# 6relayBoard.net
KiCad netlist of a schematic drawn in EAGLE
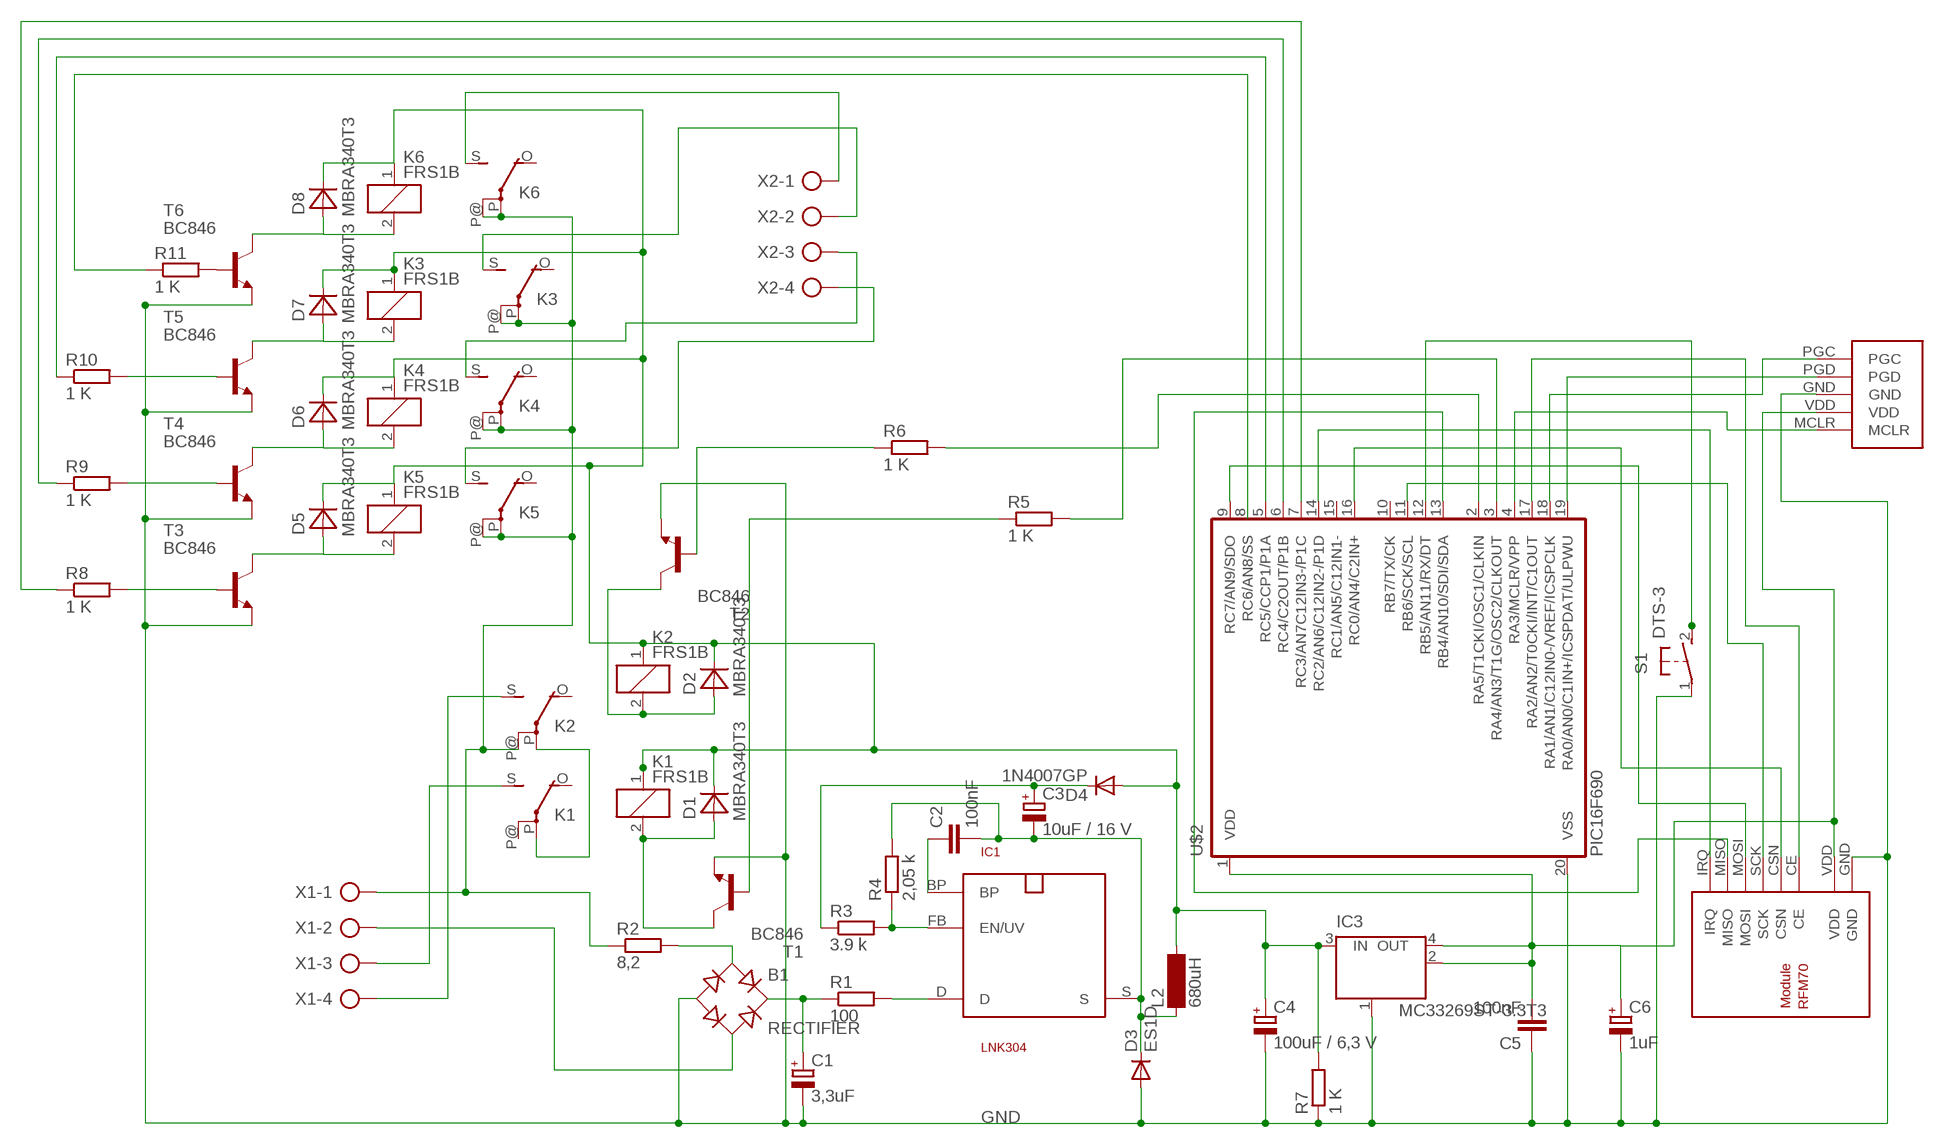
[diagram p0: schematic, sheet 1]

(export (version "E")
  (design (tool "Eeschema 10.0.6"))
  (components
    (comp (ref "B1")
      (value "RECTIFIER")
      (footprint "eagle-import:TO-269AA")
      (libsource (lib "eagle-import") (part "RECTIFIER-S40"))
    )
    (comp (ref "C1")
      (value "3,3uF")
      (footprint "eagle-import:E5-10,5")
      (libsource (lib "eagle-import") (part "CPOL-EUE5-10.5"))
    )
    (comp (ref "C2")
      (value "100nF")
      (footprint "eagle-import:C2012")
      (libsource (lib "eagle-import") (part "C-EUC2012"))
    )
    (comp (ref "C3")
      (value "10uF / 16 V")
      (footprint "eagle-import:SMC_C")
      (libsource (lib "eagle-import") (part "CPOL-EUSMCC"))
    )
    (comp (ref "C4")
      (value "100uF / 6,3 V")
      (footprint "eagle-import:E2,5-5")
      (libsource (lib "eagle-import") (part "CPOL-EUE2.5-5"))
    )
    (comp (ref "C5")
      (value "100nF")
      (footprint "eagle-import:C2012")
      (libsource (lib "eagle-import") (part "C-EUC2012"))
    )
    (comp (ref "C6")
      (value "1uF")
      (footprint "eagle-import:SMC_A")
      (libsource (lib "eagle-import") (part "CPOL-EUSMCA"))
    )
    (comp (ref "D1")
      (value "MBRA340T3")
      (footprint "eagle-import:SMA")
      (libsource (lib "eagle-import") (part "MBRA340T3"))
    )
    (comp (ref "D2")
      (value "MBRA340T3")
      (footprint "eagle-import:SMA")
      (libsource (lib "eagle-import") (part "MBRA340T3"))
    )
    (comp (ref "D3")
      (value "ES1D")
      (footprint "eagle-import:DO214AC")
      (libsource (lib "eagle-import") (part "DIODE-DO214AC"))
    )
    (comp (ref "D4")
      (value "1N4007GP")
      (footprint "eagle-import:DO214AA")
      (libsource (lib "eagle-import") (part "DIODE-DO214AA"))
    )
    (comp (ref "D5")
      (value "MBRA340T3")
      (footprint "eagle-import:SMA")
      (libsource (lib "eagle-import") (part "MBRA340T3"))
    )
    (comp (ref "D6")
      (value "MBRA340T3")
      (footprint "eagle-import:SMA")
      (libsource (lib "eagle-import") (part "MBRA340T3"))
    )
    (comp (ref "D7")
      (value "MBRA340T3")
      (footprint "eagle-import:SMA")
      (libsource (lib "eagle-import") (part "MBRA340T3"))
    )
    (comp (ref "D8")
      (value "MBRA340T3")
      (footprint "eagle-import:SMA")
      (libsource (lib "eagle-import") (part "MBRA340T3"))
    )
    (comp (ref "IC1")
      (value "LNK304")
      (footprint "eagle-import:SO-8C")
      (libsource (lib "eagle-import") (part "SO-8C"))
    )
    (comp (ref "IC3")
      (value "MC33269ST-3.3T3")
      (footprint "eagle-import:SOT223")
      (libsource (lib "eagle-import") (part "MC33269ST-3.3T3"))
    )
    (comp (ref "K1")
      (value "FRS1B")
      (footprint "eagle-import:FRS1B")
      (libsource (lib "eagle-import") (part "FRS1B"))
    )
    (comp (ref "K2")
      (value "FRS1B")
      (footprint "eagle-import:FRS1B")
      (fields (field (name "OC_FARNELL") "unknown") (field (name "OC_NEWARK") "unknown"))
      (libsource (lib "eagle-import") (part "FRS1B"))
    )
    (comp (ref "K3")
      (value "FRS1B")
      (footprint "eagle-import:FRS1B")
      (fields (field (name "OC_FARNELL") "unknown") (field (name "OC_NEWARK") "unknown"))
      (libsource (lib "eagle-import") (part "FRS1B"))
    )
    (comp (ref "K4")
      (value "FRS1B")
      (footprint "eagle-import:FRS1B")
      (fields (field (name "OC_FARNELL") "unknown") (field (name "OC_NEWARK") "unknown"))
      (libsource (lib "eagle-import") (part "FRS1B"))
    )
    (comp (ref "K5")
      (value "FRS1B")
      (footprint "eagle-import:FRS1B")
      (fields (field (name "OC_FARNELL") "unknown") (field (name "OC_NEWARK") "unknown"))
      (libsource (lib "eagle-import") (part "FRS1B"))
    )
    (comp (ref "K6")
      (value "FRS1B")
      (footprint "eagle-import:FRS1B")
      (fields (field (name "OC_FARNELL") "unknown") (field (name "OC_NEWARK") "unknown"))
      (libsource (lib "eagle-import") (part "FRS1B"))
    )
    (comp (ref "L2")
      (value "680uH")
      (footprint "eagle-import:BS11")
      (libsource (lib "eagle-import") (part "BS11"))
    )
    (comp (ref "R1")
      (value "100")
      (footprint "eagle-import:R2512W")
      (libsource (lib "eagle-import") (part "R-EU_R2512W"))
    )
    (comp (ref "R2")
      (value "8,2")
      (footprint "eagle-import:0411_12")
      (libsource (lib "eagle-import") (part "R-EU_0411/12"))
    )
    (comp (ref "R3")
      (value "3.9 k")
      (footprint "eagle-import:M2012")
      (libsource (lib "eagle-import") (part "R-EU_M2012"))
    )
    (comp (ref "R4")
      (value "2,05 k")
      (footprint "eagle-import:M2012")
      (libsource (lib "eagle-import") (part "R-EU_M2012"))
    )
    (comp (ref "R5")
      (value "1 K")
      (footprint "eagle-import:M2012")
      (libsource (lib "eagle-import") (part "R-EU_M2012"))
    )
    (comp (ref "R6")
      (value "1 K")
      (footprint "eagle-import:M2012")
      (libsource (lib "eagle-import") (part "R-EU_M2012"))
    )
    (comp (ref "R7")
      (value "1 K")
      (footprint "eagle-import:M2012")
      (libsource (lib "eagle-import") (part "R-EU_M2012"))
    )
    (comp (ref "R8")
      (value "1 K")
      (footprint "eagle-import:M2012")
      (libsource (lib "eagle-import") (part "R-EU_M2012"))
    )
    (comp (ref "R9")
      (value "1 K")
      (footprint "eagle-import:M2012")
      (libsource (lib "eagle-import") (part "R-EU_M2012"))
    )
    (comp (ref "R10")
      (value "1 K")
      (footprint "eagle-import:M2012")
      (libsource (lib "eagle-import") (part "R-EU_M2012"))
    )
    (comp (ref "R11")
      (value "1 K")
      (footprint "eagle-import:M2012")
      (libsource (lib "eagle-import") (part "R-EU_M2012"))
    )
    (comp (ref "S1")
      (value "DTS-3")
      (footprint "eagle-import:DTS-3")
      (libsource (lib "eagle-import") (part "DTS-3"))
    )
    (comp (ref "T1")
      (value "BC846")
      (footprint "eagle-import:SOT23")
      (libsource (lib "eagle-import") (part "BC846"))
    )
    (comp (ref "T2")
      (value "BC846")
      (footprint "eagle-import:SOT23")
      (libsource (lib "eagle-import") (part "BC846"))
    )
    (comp (ref "T3")
      (value "BC846")
      (footprint "eagle-import:SOT23")
      (libsource (lib "eagle-import") (part "BC846"))
    )
    (comp (ref "T4")
      (value "BC846")
      (footprint "eagle-import:SOT23")
      (libsource (lib "eagle-import") (part "BC846"))
    )
    (comp (ref "T5")
      (value "BC846")
      (footprint "eagle-import:SOT23")
      (libsource (lib "eagle-import") (part "BC846"))
    )
    (comp (ref "T6")
      (value "BC846")
      (footprint "eagle-import:SOT23")
      (libsource (lib "eagle-import") (part "BC846"))
    )
    (comp (ref "U$1")
      (value "RFM70")
      (footprint "eagle-import:RFM70")
      (libsource (lib "eagle-import") (part "RFM70"))
    )
    (comp (ref "U$2")
      (value "PIC16F690")
      (footprint "eagle-import:SSOP20")
      (libsource (lib "eagle-import") (part "PIC16F690"))
    )
    (comp (ref "U$3")
      (value "PROGRAMMINGHEADERDIP")
      (footprint "eagle-import:PROGHEADER")
      (libsource (lib "eagle-import") (part "PROGRAMMINGHEADERDIP"))
    )
    (comp (ref "X1")
      (value "AK500/4")
      (footprint "eagle-import:AK500_4")
      (libsource (lib "eagle-import") (part "AK500/4"))
    )
    (comp (ref "X2")
      (value "AK500/4")
      (footprint "eagle-import:AK500_4")
      (fields (field (name "OC_FARNELL") "unknown") (field (name "OC_NEWARK") "unknown"))
      (libsource (lib "eagle-import") (part "AK500/4"))
    )
  )
  (nets
    (net (code "1") (name "/GND") (class "Default")
      (node (ref "B1") (pin "-") (pinfunction "-_-") (pintype "passive"))
      (node (ref "C1") (pin "-") (pinfunction "-_-") (pintype "passive"))
      (node (ref "C4") (pin "-") (pinfunction "-_-") (pintype "passive"))
      (node (ref "C5") (pin "1") (pinfunction "1_1") (pintype "passive"))
      (node (ref "C6") (pin "-") (pinfunction "-_-") (pintype "passive"))
      (node (ref "D3") (pin "A") (pinfunction "A_A") (pintype "passive"))
      (node (ref "IC3") (pin "1") (pinfunction "GND/ADJ_1") (pintype "input"))
      (node (ref "R7") (pin "1") (pinfunction "1_1") (pintype "passive"))
      (node (ref "S1") (pin "1") (pinfunction "1_1") (pintype "passive"))
      (node (ref "T1") (pin "2") (pinfunction "E_2") (pintype "passive"))
      (node (ref "T2") (pin "2") (pinfunction "E_2") (pintype "passive"))
      (node (ref "T3") (pin "2") (pinfunction "E_2") (pintype "passive"))
      (node (ref "T4") (pin "2") (pinfunction "E_2") (pintype "passive"))
      (node (ref "T5") (pin "2") (pinfunction "E_2") (pintype "passive"))
      (node (ref "T6") (pin "2") (pinfunction "E_2") (pintype "passive"))
      (node (ref "U$1") (pin "GND") (pinfunction "GND_GND") (pintype "power_in"))
      (node (ref "U$2") (pin "20") (pinfunction "VSS_20") (pintype "power_in"))
      (node (ref "U$3") (pin "GND") (pinfunction "GND_GND") (pintype "power_in"))
    )
    (net (code "2") (name "Net-(B1-Pad+)") (class "Default")
      (node (ref "B1") (pin "+") (pinfunction "+_+") (pintype "passive"))
      (node (ref "C1") (pin "+") (pinfunction "+_+") (pintype "passive"))
      (node (ref "R1") (pin "1") (pinfunction "1_1") (pintype "passive"))
    )
    (net (code "3") (name "Net-(B1-PadAC1)") (class "Default")
      (node (ref "B1") (pin "AC1") (pinfunction "AC1_AC1") (pintype "passive"))
      (node (ref "R2") (pin "2") (pinfunction "2_2") (pintype "passive"))
    )
    (net (code "4") (name "Net-(C2-Pad1)") (class "Default")
      (node (ref "C2") (pin "1") (pinfunction "1_1") (pintype "passive"))
      (node (ref "IC1") (pin "BP") (pinfunction "BP_BP") (pintype "passive"))
    )
    (net (code "5") (name "Net-(C2-Pad2)") (class "Default")
      (node (ref "C2") (pin "2") (pinfunction "2_2") (pintype "passive"))
      (node (ref "C3") (pin "-") (pinfunction "-_-") (pintype "passive"))
      (node (ref "D3") (pin "C") (pinfunction "C_C") (pintype "passive"))
      (node (ref "IC1") (pin "S") (pinfunction "S_S") (pintype "power_in"))
      (node (ref "L2") (pin "1") (pinfunction "1_1") (pintype "passive"))
      (node (ref "R4") (pin "2") (pinfunction "2_2") (pintype "passive"))
    )
    (net (code "6") (name "Net-(C3-Pad+)") (class "Default")
      (node (ref "C3") (pin "+") (pinfunction "+_+") (pintype "passive"))
      (node (ref "D4") (pin "C") (pinfunction "C_C") (pintype "passive"))
      (node (ref "R3") (pin "1") (pinfunction "1_1") (pintype "passive"))
    )
    (net (code "7") (name "Net-(IC1-EN{slash}UV)") (class "Default")
      (node (ref "IC1") (pin "FB") (pinfunction "EN/UV_FB") (pintype "input"))
      (node (ref "R3") (pin "2") (pinfunction "2_2") (pintype "passive"))
      (node (ref "R4") (pin "1") (pinfunction "1_1") (pintype "passive"))
    )
    (net (code "8") (name "Net-(IC1-PadD)") (class "Default")
      (node (ref "IC1") (pin "D") (pinfunction "D_D") (pintype "open_collector"))
      (node (ref "R1") (pin "2") (pinfunction "2_2") (pintype "passive"))
    )
    (net (code "9") (name "Net-(IC3-IN)") (class "Default")
      (node (ref "C4") (pin "+") (pinfunction "+_+") (pintype "passive"))
      (node (ref "D1") (pin "C") (pinfunction "C_C") (pintype "passive"))
      (node (ref "D2") (pin "C") (pinfunction "C_C") (pintype "passive"))
      (node (ref "D4") (pin "A") (pinfunction "A_A") (pintype "passive"))
      (node (ref "D5") (pin "C") (pinfunction "C_C") (pintype "passive"))
      (node (ref "D6") (pin "C") (pinfunction "C_C") (pintype "passive"))
      (node (ref "D7") (pin "C") (pinfunction "C_C") (pintype "passive"))
      (node (ref "D8") (pin "C") (pinfunction "C_C") (pintype "passive"))
      (node (ref "IC3") (pin "3") (pinfunction "IN_3") (pintype "input"))
      (node (ref "K1") (pin "1") (pinfunction "1_1") (pintype "passive"))
      (node (ref "K2") (pin "1") (pinfunction "1_1") (pintype "passive"))
      (node (ref "K3") (pin "1") (pinfunction "1_1") (pintype "passive"))
      (node (ref "K4") (pin "1") (pinfunction "1_1") (pintype "passive"))
      (node (ref "K5") (pin "1") (pinfunction "1_1") (pintype "passive"))
      (node (ref "K6") (pin "1") (pinfunction "1_1") (pintype "passive"))
      (node (ref "L2") (pin "2") (pinfunction "2_2") (pintype "passive"))
      (node (ref "R7") (pin "2") (pinfunction "2_2") (pintype "passive"))
    )
    (net (code "10") (name "Net-(K1-PadP)") (class "Default")
      (node (ref "K1") (pin "P") (pinfunction "P_P") (pintype "passive"))
      (node (ref "K2") (pin "P") (pinfunction "P_P") (pintype "passive"))
    )
    (net (code "11") (name "Net-(T1-B)") (class "Default")
      (node (ref "R5") (pin "1") (pinfunction "1_1") (pintype "passive"))
      (node (ref "T1") (pin "1") (pinfunction "B_1") (pintype "passive"))
    )
    (net (code "12") (name "Net-(T1-C)") (class "Default")
      (node (ref "D1") (pin "A") (pinfunction "A_A") (pintype "passive"))
      (node (ref "K1") (pin "2") (pinfunction "2_2") (pintype "passive"))
      (node (ref "T1") (pin "3") (pinfunction "C_3") (pintype "passive"))
    )
    (net (code "13") (name "Net-(T2-B)") (class "Default")
      (node (ref "R6") (pin "1") (pinfunction "1_1") (pintype "passive"))
      (node (ref "T2") (pin "1") (pinfunction "B_1") (pintype "passive"))
    )
    (net (code "14") (name "Net-(T2-C)") (class "Default")
      (node (ref "D2") (pin "A") (pinfunction "A_A") (pintype "passive"))
      (node (ref "K2") (pin "2") (pinfunction "2_2") (pintype "passive"))
      (node (ref "T2") (pin "3") (pinfunction "C_3") (pintype "passive"))
    )
    (net (code "15") (name "Net-(T3-B)") (class "Default")
      (node (ref "R8") (pin "2") (pinfunction "2_2") (pintype "passive"))
      (node (ref "T3") (pin "1") (pinfunction "B_1") (pintype "passive"))
    )
    (net (code "16") (name "Net-(T3-C)") (class "Default")
      (node (ref "D5") (pin "A") (pinfunction "A_A") (pintype "passive"))
      (node (ref "K5") (pin "2") (pinfunction "2_2") (pintype "passive"))
      (node (ref "T3") (pin "3") (pinfunction "C_3") (pintype "passive"))
    )
    (net (code "17") (name "Net-(T4-B)") (class "Default")
      (node (ref "R9") (pin "2") (pinfunction "2_2") (pintype "passive"))
      (node (ref "T4") (pin "1") (pinfunction "B_1") (pintype "passive"))
    )
    (net (code "18") (name "Net-(T4-C)") (class "Default")
      (node (ref "D6") (pin "A") (pinfunction "A_A") (pintype "passive"))
      (node (ref "K4") (pin "2") (pinfunction "2_2") (pintype "passive"))
      (node (ref "T4") (pin "3") (pinfunction "C_3") (pintype "passive"))
    )
    (net (code "19") (name "Net-(T5-B)") (class "Default")
      (node (ref "R10") (pin "2") (pinfunction "2_2") (pintype "passive"))
      (node (ref "T5") (pin "1") (pinfunction "B_1") (pintype "passive"))
    )
    (net (code "20") (name "Net-(T5-C)") (class "Default")
      (node (ref "D7") (pin "A") (pinfunction "A_A") (pintype "passive"))
      (node (ref "K3") (pin "2") (pinfunction "2_2") (pintype "passive"))
      (node (ref "T5") (pin "3") (pinfunction "C_3") (pintype "passive"))
    )
    (net (code "21") (name "Net-(T6-B)") (class "Default")
      (node (ref "R11") (pin "2") (pinfunction "2_2") (pintype "passive"))
      (node (ref "T6") (pin "1") (pinfunction "B_1") (pintype "passive"))
    )
    (net (code "22") (name "Net-(T6-C)") (class "Default")
      (node (ref "D8") (pin "A") (pinfunction "A_A") (pintype "passive"))
      (node (ref "K6") (pin "2") (pinfunction "2_2") (pintype "passive"))
      (node (ref "T6") (pin "3") (pinfunction "C_3") (pintype "passive"))
    )
    (net (code "23") (name "Net-(U$2-RA0{slash}AN0{slash}C1IN+{slash}ICSPDAT{slash}ULPWU)") (class "Default")
      (node (ref "U$2") (pin "19") (pinfunction "RA0/AN0/C1IN+/ICSPDAT/ULPWU_19") (pintype "bidirectional"))
      (node (ref "U$3") (pin "PGD") (pinfunction "PGD_PGD") (pintype "bidirectional"))
    )
    (net (code "24") (name "Net-(U$2-RA1{slash}AN1{slash}C12IN0-{slash}VREF{slash}ICSPCLK)") (class "Default")
      (node (ref "U$2") (pin "18") (pinfunction "RA1/AN1/C12IN0-/VREF/ICSPCLK_18") (pintype "bidirectional"))
      (node (ref "U$3") (pin "PGC") (pinfunction "PGC_PGC") (pintype "bidirectional"))
    )
    (net (code "25") (name "Net-(U$2-RA2{slash}AN2{slash}T0CKI{slash}INT{slash}C1OUT)") (class "Default")
      (node (ref "U$1") (pin "CE") (pinfunction "CE_CE") (pintype "bidirectional"))
      (node (ref "U$2") (pin "17") (pinfunction "RA2/AN2/T0CKI/INT/C1OUT_17") (pintype "bidirectional"))
    )
    (net (code "26") (name "Net-(U$2-RA3{slash}MCLR{slash}VPP)") (class "Default")
      (node (ref "U$2") (pin "4") (pinfunction "RA3/MCLR/VPP_4") (pintype "bidirectional"))
      (node (ref "U$3") (pin "MCLR") (pinfunction "MCLR_MCLR") (pintype "output"))
    )
    (net (code "27") (name "Net-(U$2-RA4{slash}AN3{slash}T1G{slash}OSC2{slash}CLKOUT)") (class "Default")
      (node (ref "R5") (pin "2") (pinfunction "2_2") (pintype "passive"))
      (node (ref "U$2") (pin "3") (pinfunction "RA4/AN3/T1G/OSC2/CLKOUT_3") (pintype "bidirectional"))
    )
    (net (code "28") (name "Net-(U$2-RA5{slash}T1CKI{slash}OSC1{slash}CLKIN)") (class "Default")
      (node (ref "R6") (pin "2") (pinfunction "2_2") (pintype "passive"))
      (node (ref "U$2") (pin "2") (pinfunction "RA5/T1CKI/OSC1/CLKIN_2") (pintype "bidirectional"))
    )
    (net (code "29") (name "Net-(U$2-RB4{slash}AN10{slash}SDI{slash}SDA)") (class "Default")
      (node (ref "U$1") (pin "MISO") (pinfunction "MISO_MISO") (pintype "bidirectional"))
      (node (ref "U$2") (pin "13") (pinfunction "RB4/AN10/SDI/SDA_13") (pintype "bidirectional"))
    )
    (net (code "30") (name "Net-(U$2-RB5{slash}AN11{slash}RX{slash}DT)") (class "Default")
      (node (ref "S1") (pin "2") (pinfunction "2_2") (pintype "passive"))
      (node (ref "U$2") (pin "12") (pinfunction "RB5/AN11/RX/DT_12") (pintype "bidirectional"))
    )
    (net (code "31") (name "Net-(U$2-RB6{slash}SCK{slash}SCL)") (class "Default")
      (node (ref "U$1") (pin "SCK") (pinfunction "SCK_SCK") (pintype "bidirectional"))
      (node (ref "U$2") (pin "11") (pinfunction "RB6/SCK/SCL_11") (pintype "bidirectional"))
    )
    (net (code "32") (name "Net-(U$2-RC0{slash}AN4{slash}C2IN+)") (class "Default")
      (node (ref "U$1") (pin "CSN") (pinfunction "CSN_CSN") (pintype "bidirectional"))
      (node (ref "U$2") (pin "16") (pinfunction "RC0/AN4/C2IN+_16") (pintype "bidirectional"))
    )
    (net (code "33") (name "Net-(U$2-RC2{slash}AN6{slash}C12IN2-{slash}P1D)") (class "Default")
      (node (ref "U$1") (pin "IRQ") (pinfunction "IRQ_IRQ") (pintype "bidirectional"))
      (node (ref "U$2") (pin "14") (pinfunction "RC2/AN6/C12IN2-/P1D_14") (pintype "bidirectional"))
    )
    (net (code "34") (name "Net-(U$2-RC3{slash}AN7C12IN3-{slash}P1C)") (class "Default")
      (node (ref "R8") (pin "1") (pinfunction "1_1") (pintype "passive"))
      (node (ref "U$2") (pin "7") (pinfunction "RC3/AN7C12IN3-/P1C_7") (pintype "bidirectional"))
    )
    (net (code "35") (name "Net-(U$2-RC4{slash}C2OUT{slash}P1B)") (class "Default")
      (node (ref "R9") (pin "1") (pinfunction "1_1") (pintype "passive"))
      (node (ref "U$2") (pin "6") (pinfunction "RC4/C2OUT/P1B_6") (pintype "bidirectional"))
    )
    (net (code "36") (name "Net-(U$2-RC5{slash}CCP1{slash}P1A)") (class "Default")
      (node (ref "R10") (pin "1") (pinfunction "1_1") (pintype "passive"))
      (node (ref "U$2") (pin "5") (pinfunction "RC5/CCP1/P1A_5") (pintype "bidirectional"))
    )
    (net (code "37") (name "Net-(U$2-RC6{slash}AN8{slash}SS)") (class "Default")
      (node (ref "R11") (pin "1") (pinfunction "1_1") (pintype "passive"))
      (node (ref "U$2") (pin "8") (pinfunction "RC6/AN8/SS_8") (pintype "bidirectional"))
    )
    (net (code "38") (name "Net-(U$2-RC7{slash}AN9{slash}SDO)") (class "Default")
      (node (ref "U$1") (pin "MOSI") (pinfunction "MOSI_MOSI") (pintype "bidirectional"))
      (node (ref "U$2") (pin "9") (pinfunction "RC7/AN9/SDO_9") (pintype "bidirectional"))
    )
    (net (code "39") (name "Net-(U$2-VDD)") (class "Default")
      (node (ref "C5") (pin "2") (pinfunction "2_2") (pintype "passive"))
      (node (ref "C6") (pin "+") (pinfunction "+_+") (pintype "passive"))
      (node (ref "IC3") (pin "2") (pinfunction "OUT_2") (pintype "passive"))
      (node (ref "IC3") (pin "4") (pinfunction "OUT_4") (pintype "passive"))
      (node (ref "U$1") (pin "VDD") (pinfunction "VDD_VDD") (pintype "power_in"))
      (node (ref "U$2") (pin "1") (pinfunction "VDD_1") (pintype "power_in"))
      (node (ref "U$3") (pin "VDD") (pinfunction "VDD_VDD") (pintype "power_in"))
    )
    (net (code "40") (name "Net-(X1A-KL)") (class "Default")
      (node (ref "K2") (pin "P@") (pinfunction "P_P@") (pintype "passive"))
      (node (ref "K3") (pin "P") (pinfunction "P_P") (pintype "passive"))
      (node (ref "K3") (pin "P@") (pinfunction "P_P@") (pintype "passive"))
      (node (ref "K4") (pin "P") (pinfunction "P_P") (pintype "passive"))
      (node (ref "K4") (pin "P@") (pinfunction "P_P@") (pintype "passive"))
      (node (ref "K5") (pin "P") (pinfunction "P_P") (pintype "passive"))
      (node (ref "K5") (pin "P@") (pinfunction "P_P@") (pintype "passive"))
      (node (ref "K6") (pin "P") (pinfunction "P_P") (pintype "passive"))
      (node (ref "K6") (pin "P@") (pinfunction "P_P@") (pintype "passive"))
      (node (ref "R2") (pin "1") (pinfunction "1_1") (pintype "passive"))
      (node (ref "X1") (pin "1") (pinfunction "KL_1") (pintype "passive"))
    )
    (net (code "41") (name "Net-(X1B-KL)") (class "Default")
      (node (ref "B1") (pin "AC2") (pinfunction "AC2_AC2") (pintype "passive"))
      (node (ref "X1") (pin "2") (pinfunction "KL_2") (pintype "passive"))
    )
    (net (code "42") (name "Net-(X1C-KL)") (class "Default")
      (node (ref "K1") (pin "S") (pinfunction "S_S") (pintype "passive"))
      (node (ref "X1") (pin "3") (pinfunction "KL_3") (pintype "passive"))
    )
    (net (code "43") (name "Net-(X1D-KL)") (class "Default")
      (node (ref "K2") (pin "S") (pinfunction "S_S") (pintype "passive"))
      (node (ref "X1") (pin "4") (pinfunction "KL_4") (pintype "passive"))
    )
    (net (code "44") (name "Net-(X2A-KL)") (class "Default")
      (node (ref "K6") (pin "S") (pinfunction "S_S") (pintype "passive"))
      (node (ref "X2") (pin "1") (pinfunction "KL_1") (pintype "passive"))
    )
    (net (code "45") (name "Net-(X2B-KL)") (class "Default")
      (node (ref "K3") (pin "S") (pinfunction "S_S") (pintype "passive"))
      (node (ref "X2") (pin "2") (pinfunction "KL_2") (pintype "passive"))
    )
    (net (code "46") (name "Net-(X2C-KL)") (class "Default")
      (node (ref "K4") (pin "S") (pinfunction "S_S") (pintype "passive"))
      (node (ref "X2") (pin "3") (pinfunction "KL_3") (pintype "passive"))
    )
    (net (code "47") (name "Net-(X2D-KL)") (class "Default")
      (node (ref "K5") (pin "S") (pinfunction "S_S") (pintype "passive"))
      (node (ref "X2") (pin "4") (pinfunction "KL_4") (pintype "passive"))
    )
    (net (code "48") (name "unconnected-(K1-PadO)") (class "Default")
      (node (ref "K1") (pin "O") (pinfunction "O_O") (pintype "passive"))
    )
    (net (code "49") (name "unconnected-(K1B-P-PadP@)") (class "Default")
      (node (ref "K1") (pin "P@") (pinfunction "P_P@") (pintype "passive"))
    )
    (net (code "50") (name "unconnected-(K2-PadO)") (class "Default")
      (node (ref "K2") (pin "O") (pinfunction "O_O") (pintype "passive"))
    )
    (net (code "51") (name "unconnected-(K3-PadO)") (class "Default")
      (node (ref "K3") (pin "O") (pinfunction "O_O") (pintype "passive"))
    )
    (net (code "52") (name "unconnected-(K4-PadO)") (class "Default")
      (node (ref "K4") (pin "O") (pinfunction "O_O") (pintype "passive"))
    )
    (net (code "53") (name "unconnected-(K5-PadO)") (class "Default")
      (node (ref "K5") (pin "O") (pinfunction "O_O") (pintype "passive"))
    )
    (net (code "54") (name "unconnected-(K6-PadO)") (class "Default")
      (node (ref "K6") (pin "O") (pinfunction "O_O") (pintype "passive"))
    )
    (net (code "55") (name "unconnected-(U$2-RB7{slash}TX{slash}CK-Pad10)") (class "Default")
      (node (ref "U$2") (pin "10") (pinfunction "RB7/TX/CK_10") (pintype "bidirectional"))
    )
    (net (code "56") (name "unconnected-(U$2-RC1{slash}AN5{slash}C12IN1--Pad15)") (class "Default")
      (node (ref "U$2") (pin "15") (pinfunction "RC1/AN5/C12IN1-_15") (pintype "bidirectional"))
    )
  )
)
